# lm3410-boost-flashlight-driver-20mm-mk-1.net
KiCad netlist of a schematic drawn in EAGLE
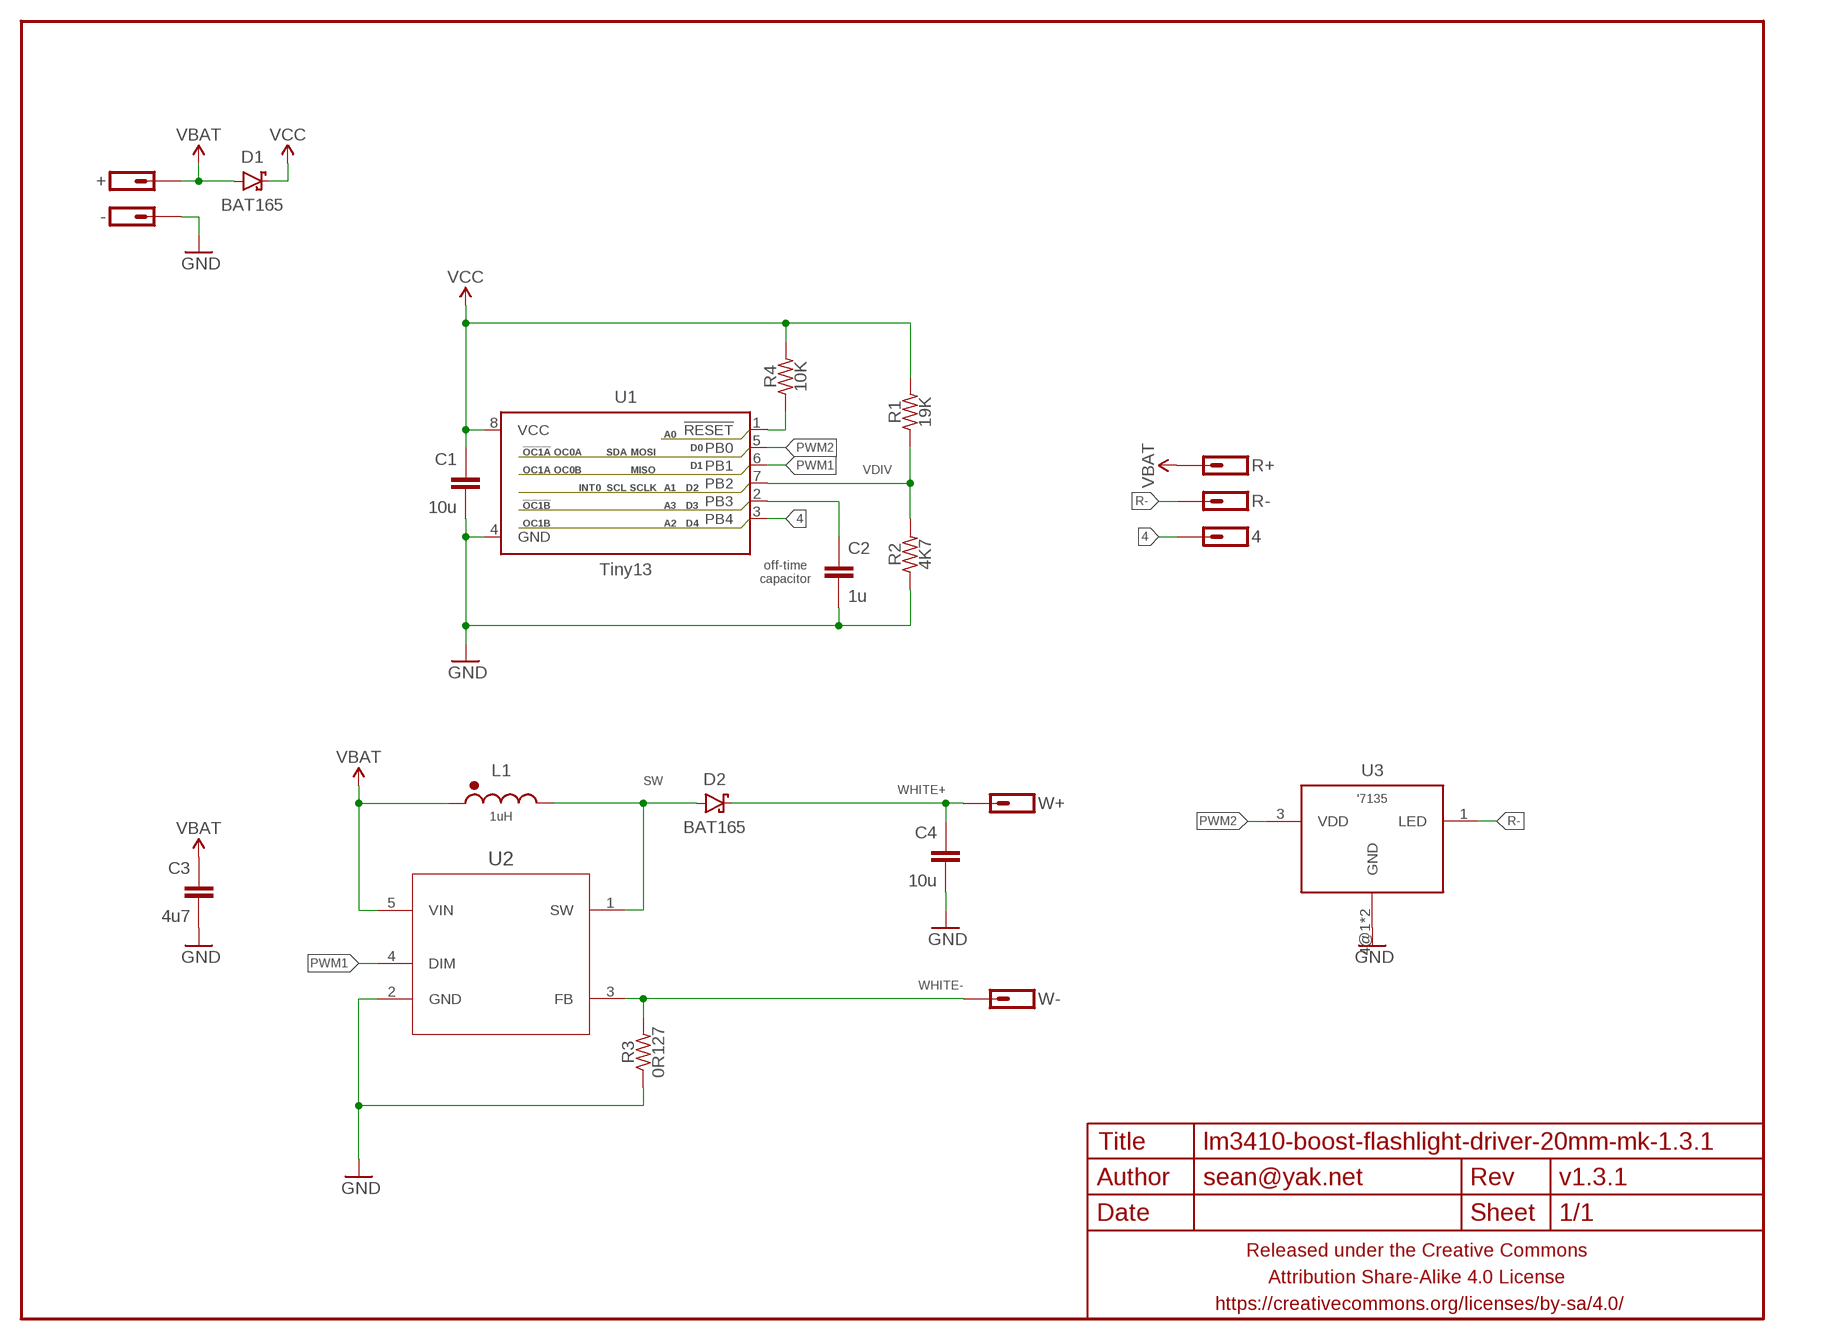
[diagram p0: schematic, sheet 1]

(export (version "E")
  (design (tool "Eeschema 10.0.6"))
  (components
    (comp (ref "+")
      (value "M01PTH-1MM-CIR-NS")
      (footprint "eagle-import:1X01-1MM-CIR-NS")
      (libsource (lib "eagle-import") (part "M01PTH-1MM-CIR-NS"))
    )
    (comp (ref "-")
      (value "M01NOT-A-VIA-NOPE")
      (footprint "eagle-import:1X01_NOSILK_NOSTOP")
      (libsource (lib "eagle-import") (part "M01NOT-A-VIA-NOPE"))
    )
    (comp (ref "4")
      (value "M01SMD-1MM-DIA-NS")
      (footprint "eagle-import:1X01-SMD-1MM-DIA-NS")
      (libsource (lib "eagle-import") (part "M01SMD-1MM-DIA-NS"))
    )
    (comp (ref "C1")
      (value "10u")
      (footprint "eagle-import:C0603-TIGHTER")
      (libsource (lib "eagle-import") (part "CAPACITOR-CERAMICC0603-TIGHTER"))
    )
    (comp (ref "C2")
      (value "1u")
      (footprint "eagle-import:C0603-TIGHTER")
      (libsource (lib "eagle-import") (part "CAPACITOR-CERAMICC0603-TIGHTER"))
    )
    (comp (ref "C3")
      (value "4u7")
      (footprint "eagle-import:C0603-TIGHTER")
      (libsource (lib "eagle-import") (part "CAPACITOR-CERAMICC0603-TIGHTER"))
    )
    (comp (ref "C4")
      (value "10u")
      (footprint "eagle-import:C0603-TIGHTER")
      (libsource (lib "eagle-import") (part "CAPACITOR-CERAMICC0603-TIGHTER"))
    )
    (comp (ref "D1")
      (value "BAT165")
      (footprint "eagle-import:SOD323-SCHOTTKY")
      (libsource (lib "eagle-import") (part "DIODE-SCHOTTKYSOD323"))
    )
    (comp (ref "D2")
      (value "BAT165")
      (footprint "eagle-import:SOD123-SCHOTTKY")
      (libsource (lib "eagle-import") (part "DIODE-SCHOTTKYSOD123"))
    )
    (comp (ref "FRAME1")
      (value "FRAME-LETTERNO_PACKAGE")
      (footprint "eagle-import:DUMMY")
      (fields (field (name "DESIGNER") "sean@yak.net") (field (name "VERSION") "v1.3.1"))
      (libsource (lib "eagle-import") (part "FRAME-LETTERNO_PACKAGE"))
    )
    (comp (ref "L1")
      (value "1uH")
      (footprint "eagle-import:PFL2512")
      (libsource (lib "eagle-import") (part "INDUCTORPFL2512"))
    )
    (comp (ref "R+")
      (value "M01SMD-1MM-DIA-NS")
      (footprint "eagle-import:1X01-SMD-1MM-DIA-NS")
      (libsource (lib "eagle-import") (part "M01SMD-1MM-DIA-NS"))
    )
    (comp (ref "R-")
      (value "M01SMD-1MM-DIA-NS")
      (footprint "eagle-import:1X01-SMD-1MM-DIA-NS")
      (libsource (lib "eagle-import") (part "M01SMD-1MM-DIA-NS"))
    )
    (comp (ref "R1")
      (value "19K")
      (footprint "eagle-import:R0603-TIGHTER")
      (libsource (lib "eagle-import") (part "RESISTORR0603-TIGHTER"))
    )
    (comp (ref "R2")
      (value "4K7")
      (footprint "eagle-import:R0603-TIGHTER")
      (libsource (lib "eagle-import") (part "RESISTORR0603-TIGHTER"))
    )
    (comp (ref "R3")
      (value "0R127")
      (footprint "eagle-import:R0805")
      (libsource (lib "eagle-import") (part "RESISTORR0805"))
    )
    (comp (ref "R4")
      (value "10K")
      (footprint "eagle-import:R0402")
      (libsource (lib "eagle-import") (part "RESISTORR0402"))
    )
    (comp (ref "U1")
      (value "Tiny13")
      (footprint "eagle-import:SO08-NARROWER")
      (libsource (lib "eagle-import") (part "ATTINY13SOIC-NARROWPADS"))
    )
    (comp (ref "U2")
      (value "LM3410XMF")
      (footprint "eagle-import:SOT95P285X120-5N")
      (libsource (lib "eagle-import") (part "LM3410XMF"))
    )
    (comp (ref "U3")
      (value "'7135")
      (footprint "eagle-import:SOT89-NOTHERM")
      (libsource (lib "eagle-import") (part "AMC7135SOT-89-NOTHERM"))
    )
    (comp (ref "W+")
      (value "M01PTH-1.2MM-NS")
      (footprint "eagle-import:1X01-1.2MM-NS")
      (libsource (lib "eagle-import") (part "M01PTH-1.2MM-NS"))
    )
    (comp (ref "W-")
      (value "M01PTH-1.2MM-NS")
      (footprint "eagle-import:1X01-1.2MM-NS")
      (libsource (lib "eagle-import") (part "M01PTH-1.2MM-NS"))
    )
  )
  (nets
    (net (code "1") (name "/SW") (class "Default")
      (node (ref "D2") (pin "A") (pinfunction "A_A") (pintype "passive"))
      (node (ref "L1") (pin "P$2") (pinfunction "2_P$2") (pintype "passive"))
      (node (ref "U2") (pin "1") (pinfunction "SW_1") (pintype "output"))
    )
    (net (code "2") (name "/VDIV") (class "Default")
      (node (ref "R1") (pin "1") (pinfunction "1_1") (pintype "passive"))
      (node (ref "R2") (pin "2") (pinfunction "2_2") (pintype "passive"))
      (node (ref "U1") (pin "7") (pinfunction "PB2_7") (pintype "bidirectional"))
    )
    (net (code "3") (name "/WHITE+") (class "Default")
      (node (ref "C4") (pin "1") (pinfunction "1_1") (pintype "passive"))
      (node (ref "D2") (pin "C") (pinfunction "C_C") (pintype "passive"))
      (node (ref "W+") (pin "P$1") (pinfunction "1_P$1") (pintype "passive"))
    )
    (net (code "4") (name "/WHITE-") (class "Default")
      (node (ref "R3") (pin "2") (pinfunction "2_2") (pintype "passive"))
      (node (ref "U2") (pin "3") (pinfunction "FB_3") (pintype "input"))
      (node (ref "W-") (pin "P$1") (pinfunction "1_P$1") (pintype "passive"))
    )
    (net (code "5") (name "4") (class "Default")
      (node (ref "4") (pin "P$1") (pinfunction "1_P$1") (pintype "passive"))
      (node (ref "U1") (pin "3") (pinfunction "PB4_3") (pintype "bidirectional"))
    )
    (net (code "6") (name "GND") (class "Default")
      (node (ref "-") (pin "P$1") (pinfunction "1_P$1") (pintype "passive"))
      (node (ref "C1") (pin "2") (pinfunction "2_2") (pintype "passive"))
      (node (ref "C2") (pin "2") (pinfunction "2_2") (pintype "passive"))
      (node (ref "C3") (pin "2") (pinfunction "2_2") (pintype "passive"))
      (node (ref "C4") (pin "2") (pinfunction "2_2") (pintype "passive"))
      (node (ref "R2") (pin "1") (pinfunction "1_1") (pintype "passive"))
      (node (ref "R3") (pin "1") (pinfunction "1_1") (pintype "passive"))
      (node (ref "U1") (pin "4") (pinfunction "GND_4") (pintype "bidirectional"))
      (node (ref "U2") (pin "2") (pinfunction "GND_2") (pintype "passive"))
      (node (ref "U3") (pin "4@1") (pinfunction "GND_4@1") (pintype "bidirectional"))
      (node (ref "U3") (pin "4@2") (pinfunction "GND_4@2") (pintype "bidirectional"))
    )
    (net (code "7") (name "Net-(U1-PB3)") (class "Default")
      (node (ref "C2") (pin "1") (pinfunction "1_1") (pintype "passive"))
      (node (ref "U1") (pin "2") (pinfunction "PB3_2") (pintype "bidirectional"))
    )
    (net (code "8") (name "Net-(U1-~{RESET})") (class "Default")
      (node (ref "R4") (pin "1") (pinfunction "1_1") (pintype "passive"))
      (node (ref "U1") (pin "1") (pinfunction "~{RESET}_1") (pintype "bidirectional"))
    )
    (net (code "9") (name "PWM1") (class "Default")
      (node (ref "U1") (pin "6") (pinfunction "PB1_6") (pintype "bidirectional"))
      (node (ref "U2") (pin "4") (pinfunction "DIM_4") (pintype "input"))
    )
    (net (code "10") (name "PWM2") (class "Default")
      (node (ref "U1") (pin "5") (pinfunction "PB0_5") (pintype "bidirectional"))
      (node (ref "U3") (pin "3") (pinfunction "VDD_3") (pintype "bidirectional"))
    )
    (net (code "11") (name "R-") (class "Default")
      (node (ref "R-") (pin "P$1") (pinfunction "1_P$1") (pintype "passive"))
      (node (ref "U3") (pin "1") (pinfunction "LED_1") (pintype "bidirectional"))
    )
    (net (code "12") (name "VBAT") (class "Default")
      (node (ref "+") (pin "1") (pinfunction "1_1") (pintype "passive"))
      (node (ref "C3") (pin "1") (pinfunction "1_1") (pintype "passive"))
      (node (ref "D1") (pin "A") (pinfunction "A_A") (pintype "passive"))
      (node (ref "L1") (pin "P$1") (pinfunction "1_P$1") (pintype "passive"))
      (node (ref "R+") (pin "P$1") (pinfunction "1_P$1") (pintype "passive"))
      (node (ref "U2") (pin "5") (pinfunction "VIN_5") (pintype "power_in"))
    )
    (net (code "13") (name "VCC") (class "Default")
      (node (ref "C1") (pin "1") (pinfunction "1_1") (pintype "passive"))
      (node (ref "D1") (pin "C") (pinfunction "C_C") (pintype "passive"))
      (node (ref "R1") (pin "2") (pinfunction "2_2") (pintype "passive"))
      (node (ref "R4") (pin "2") (pinfunction "2_2") (pintype "passive"))
      (node (ref "U1") (pin "8") (pinfunction "VCC_8") (pintype "bidirectional"))
    )
  )
)
